# headers.net
KiCad netlist of a schematic drawn in Altium Designer
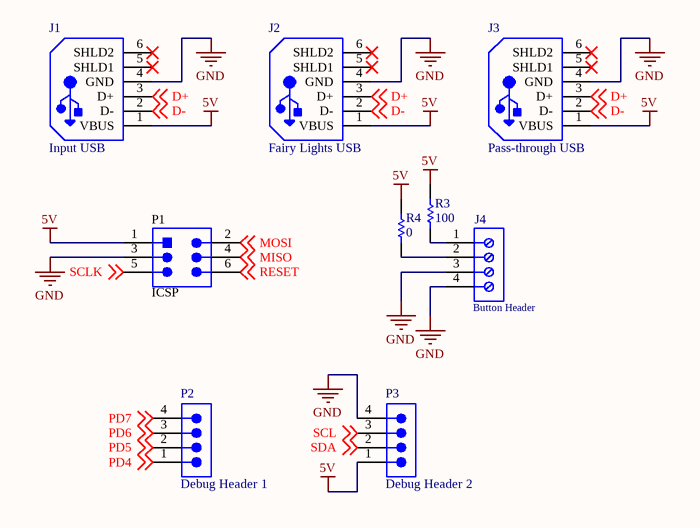
[diagram p0: headers.SchDoc]

(export (version "E")
  (design (tool "Eeschema 10.0.6"))
  (components
    (comp (ref "J1")
      (value "Input USB")
      (footprint "TE-292303-1_V")
      (fields (field (name "MANUFACTURER") "TE Connectivity") (field (name "MPN") "292303-1"))
      (libsource (lib "Altium Content Vault") (part "USB-4-2SHLD"))
    )
    (comp (ref "J2")
      (value "Fairy Lights USB")
      (footprint "TE-292303-1_V")
      (fields (field (name "MANUFACTURER") "TE Connectivity") (field (name "MPN") "292303-1"))
      (libsource (lib "Altium Content Vault") (part "USB-4-2SHLD"))
    )
    (comp (ref "J3")
      (value "Pass-through USB")
      (footprint "TE-292303-1_V")
      (fields (field (name "MANUFACTURER") "TE Connectivity") (field (name "MPN") "292303-1"))
      (libsource (lib "Altium Content Vault") (part "USB-4-2SHLD"))
    )
    (comp (ref "J4")
      (value "Button Header")
      (footprint "691508110304")
      (description "Serie 5081 - 3.50 mm Horizontal Entry SMT with Rising Cage Clamp WR-TBL, 4 pin")
      (fields
        (field (name "PART NUMBER") "691508110304")
        (field (name "MANUFACTURER") "Wurth Elektronik")
        (field (name "PUBLISHER") "WurthElektronik")
      )
      (libsource (lib "Altium Content Vault") (part "WE-CN-1P-F-TB4"))
    )
    (comp (ref "P1")
      (value "ICSP")
      (footprint "SMTC-TSW-103-08-L-D_V")
      (fields (field (name "MANUFACTURER") "Samtec") (field (name "MPN") "TSW-103-08-L-D"))
      (libsource (lib "Altium Content Vault") (part "CN-2P-M-R6"))
    )
    (comp (ref "P2")
      (value "Debug Header 1")
      (footprint "SMTC-TSW-104-08-X-S")
      (description "0.025\" SQ Post Header, Through-hole, Vertical, -55 to 105 degC, 2.54 mm Pitch, 4-Pin, Male, RoHS")
      (fields (field (name "PARTNUMBER") "TSW-104-08-T-S") (field (name "MANUFACTURER") "Samtec"))
      (libsource (lib "Altium Content Vault") (part "SMTC-TSW-104-08-X-S"))
    )
    (comp (ref "P3")
      (value "Debug Header 2")
      (footprint "SMTC-TSW-104-08-X-S")
      (description "0.025\" SQ Post Header, Through-hole, Vertical, -55 to 105 degC, 2.54 mm Pitch, 4-Pin, Male, RoHS")
      (fields (field (name "PARTNUMBER") "TSW-104-08-T-S") (field (name "MANUFACTURER") "Samtec"))
      (libsource (lib "Altium Content Vault") (part "SMTC-TSW-104-08-X-S"))
    )
    (comp (ref "R3")
      (value "100")
      (footprint "RESC2013X50X30LL20T20")
      (fields (field (name "MANUFACTURER") "Vishay Dale") (field (name "PART NUMBER") "CRCW0805100RFKEA"))
      (libsource (lib "Altium Content Vault") (part "RES"))
    )
    (comp (ref "R4")
      (value "0")
      (footprint "RESC2013X50X30LL20T20")
      (fields (field (name "MANUFACTURER") "Vishay Dale") (field (name "PART NUMBER") "CRCW08050000Z0EA"))
      (libsource (lib "Altium Content Vault") (part "RES"))
    )
  )
  (nets
    (net (code "1") (name "5V") (class "Default")
      (node (ref "J1") (pin "1") (pinfunction "VBUS_1") (pintype "passive"))
      (node (ref "J2") (pin "1") (pinfunction "VBUS_1") (pintype "passive"))
      (node (ref "J3") (pin "1") (pinfunction "VBUS_1") (pintype "passive"))
      (node (ref "P1") (pin "1") (pinfunction "1_1") (pintype "passive"))
      (node (ref "P3") (pin "1") (pinfunction "1_1") (pintype "passive"))
      (node (ref "R3") (pin "2") (pinfunction "2_2") (pintype "passive"))
      (node (ref "R4") (pin "2") (pinfunction "2_2") (pintype "passive"))
    )
    (net (code "2") (name "D+") (class "Default")
      (node (ref "J1") (pin "3") (pinfunction "D+_3") (pintype "passive"))
      (node (ref "J2") (pin "3") (pinfunction "D+_3") (pintype "passive"))
      (node (ref "J3") (pin "3") (pinfunction "D+_3") (pintype "passive"))
    )
    (net (code "3") (name "D-") (class "Default")
      (node (ref "J1") (pin "2") (pinfunction "D-_2") (pintype "passive"))
      (node (ref "J2") (pin "2") (pinfunction "D-_2") (pintype "passive"))
      (node (ref "J3") (pin "2") (pinfunction "D-_2") (pintype "passive"))
    )
    (net (code "4") (name "GND") (class "Default")
      (node (ref "J1") (pin "4") (pinfunction "GND_4") (pintype "passive"))
      (node (ref "J2") (pin "4") (pinfunction "GND_4") (pintype "passive"))
      (node (ref "J3") (pin "4") (pinfunction "GND_4") (pintype "passive"))
      (node (ref "J4") (pin "3") (pinfunction "3_3") (pintype "passive"))
      (node (ref "J4") (pin "4") (pinfunction "4_4") (pintype "passive"))
      (node (ref "P1") (pin "3") (pinfunction "3_3") (pintype "passive"))
      (node (ref "P3") (pin "4") (pinfunction "4_4") (pintype "passive"))
    )
    (net (code "5") (name "MISO") (class "Default")
      (node (ref "P1") (pin "4") (pinfunction "4_4") (pintype "passive"))
    )
    (net (code "6") (name "MOSI") (class "Default")
      (node (ref "P1") (pin "2") (pinfunction "2_2") (pintype "passive"))
    )
    (net (code "7") (name "Net-(J4-Pad1)") (class "Default")
      (node (ref "J4") (pin "1") (pinfunction "1_1") (pintype "passive"))
      (node (ref "R3") (pin "1") (pinfunction "1_1") (pintype "passive"))
    )
    (net (code "8") (name "Net-(J4-Pad2)") (class "Default")
      (node (ref "J4") (pin "2") (pinfunction "2_2") (pintype "passive"))
      (node (ref "R4") (pin "1") (pinfunction "1_1") (pintype "passive"))
    )
    (net (code "9") (name "PD4") (class "Default")
      (node (ref "P2") (pin "1") (pinfunction "1_1") (pintype "passive"))
    )
    (net (code "10") (name "PD5") (class "Default")
      (node (ref "P2") (pin "2") (pinfunction "2_2") (pintype "passive"))
    )
    (net (code "11") (name "PD6") (class "Default")
      (node (ref "P2") (pin "3") (pinfunction "3_3") (pintype "passive"))
    )
    (net (code "12") (name "PD7") (class "Default")
      (node (ref "P2") (pin "4") (pinfunction "4_4") (pintype "passive"))
    )
    (net (code "13") (name "RESET") (class "Default")
      (node (ref "P1") (pin "6") (pinfunction "6_6") (pintype "passive"))
    )
    (net (code "14") (name "SCL") (class "Default")
      (node (ref "P3") (pin "3") (pinfunction "3_3") (pintype "passive"))
    )
    (net (code "15") (name "SCLK") (class "Default")
      (node (ref "P1") (pin "5") (pinfunction "5_5") (pintype "passive"))
    )
    (net (code "16") (name "SDA") (class "Default")
      (node (ref "P3") (pin "2") (pinfunction "2_2") (pintype "passive"))
    )
    (net (code "17") (name "unconnected-(J1-SHLD1-Pad5)") (class "Default")
      (node (ref "J1") (pin "5") (pinfunction "SHLD1_5") (pintype "passive+no_connect"))
    )
    (net (code "18") (name "unconnected-(J1-SHLD2-Pad6)") (class "Default")
      (node (ref "J1") (pin "6") (pinfunction "SHLD2_6") (pintype "passive+no_connect"))
    )
    (net (code "19") (name "unconnected-(J2-SHLD1-Pad5)") (class "Default")
      (node (ref "J2") (pin "5") (pinfunction "SHLD1_5") (pintype "passive+no_connect"))
    )
    (net (code "20") (name "unconnected-(J2-SHLD2-Pad6)") (class "Default")
      (node (ref "J2") (pin "6") (pinfunction "SHLD2_6") (pintype "passive+no_connect"))
    )
    (net (code "21") (name "unconnected-(J3-SHLD1-Pad5)") (class "Default")
      (node (ref "J3") (pin "5") (pinfunction "SHLD1_5") (pintype "passive+no_connect"))
    )
    (net (code "22") (name "unconnected-(J3-SHLD2-Pad6)") (class "Default")
      (node (ref "J3") (pin "6") (pinfunction "SHLD2_6") (pintype "passive+no_connect"))
    )
  )
)
